# SunS_sensor.net
KiCad netlist of a schematic drawn in Altium Designer
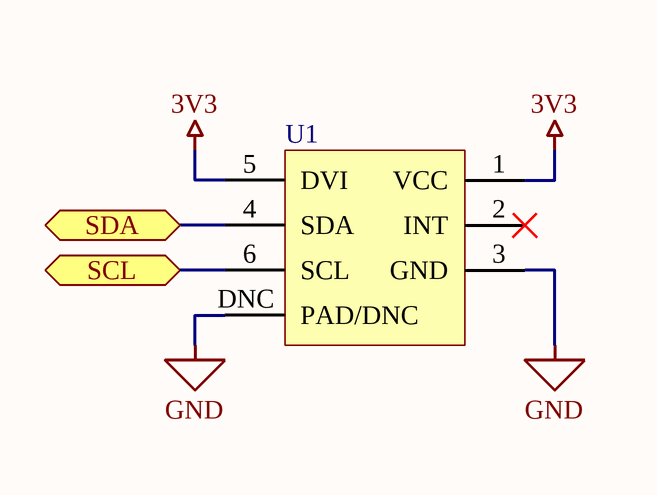
[diagram p0: SunS_sensor.SchDoc]

(export (version "E")
  (design (tool "Eeschema 10.0.6"))
  (components
    (comp (ref "U1")
      (value "BH1730FVC")
      (footprint "WSOF6")
      (description "Digital 16bit Serial Output Type  Ambient Light Sensor IC")
      (fields (field (name "MANUFACTURER") "ROHM") (field (name "MANUFACTURERPARTNUMBER") "BH1730FVC"))
      (libsource (lib "microcircuits") (part "BH1730FVC"))
    )
  )
  (nets
    (net (code "1") (name "/SCL") (class "Default")
      (node (ref "U1") (pin "6") (pinfunction "SCL_6") (pintype "open_collector"))
    )
    (net (code "2") (name "/SDA") (class "Default")
      (node (ref "U1") (pin "4") (pinfunction "SDA_4") (pintype "open_collector"))
    )
    (net (code "3") (name "3V3") (class "Default")
      (node (ref "U1") (pin "1") (pinfunction "VCC_1") (pintype "power_in"))
      (node (ref "U1") (pin "5") (pinfunction "DVI_5") (pintype "passive"))
    )
    (net (code "4") (name "GND") (class "Default")
      (node (ref "U1") (pin "3") (pinfunction "GND_3") (pintype "power_in"))
      (node (ref "U1") (pin "DNC") (pinfunction "PAD/DNC_DNC") (pintype "passive"))
    )
    (net (code "5") (name "unconnected-(U1-INT-Pad2)") (class "Default")
      (node (ref "U1") (pin "2") (pinfunction "INT_2") (pintype "open_collector+no_connect"))
    )
  )
)
